# ArduinoLogger.net
KiCad netlist of a schematic drawn in EAGLE
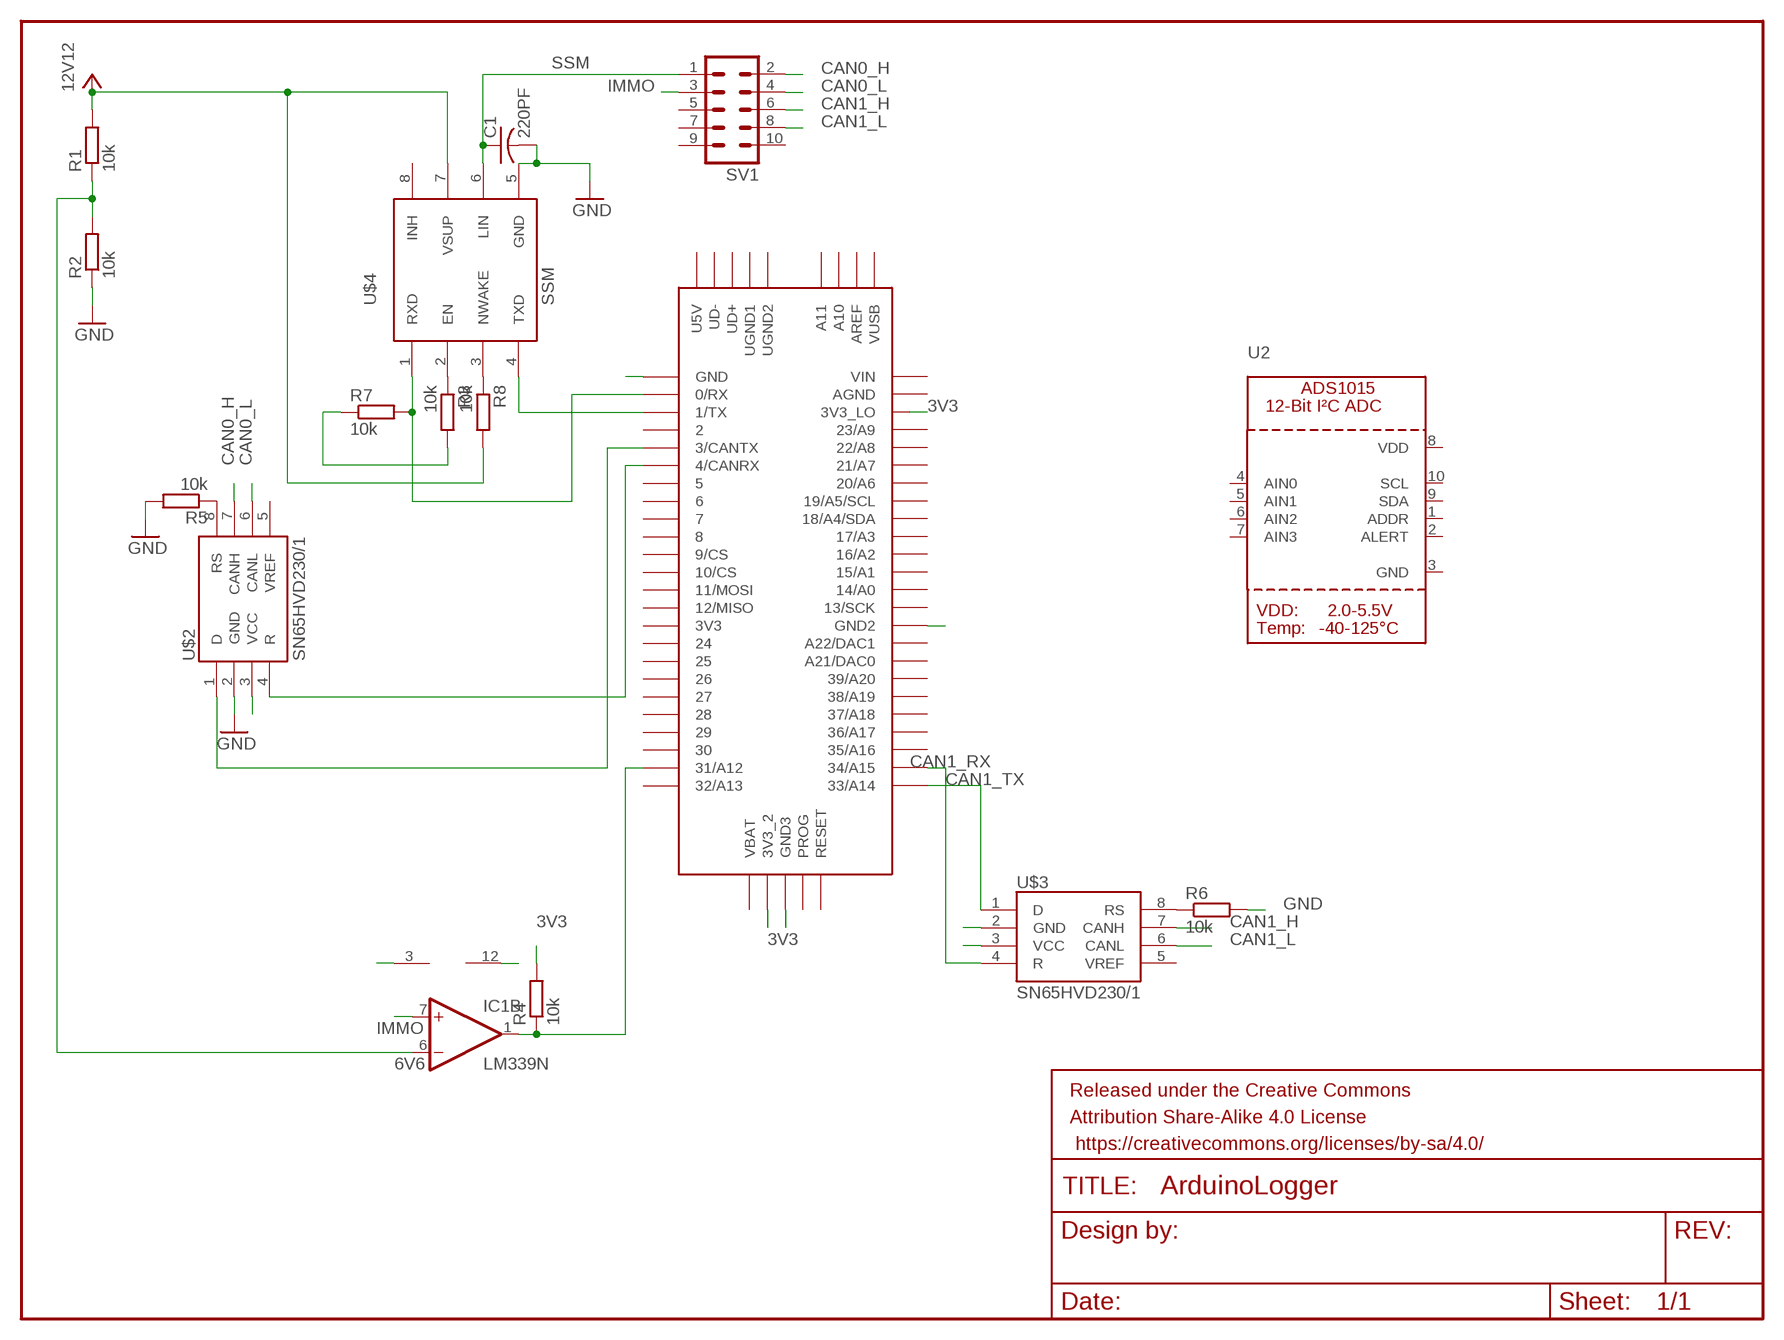
[diagram p0: schematic, sheet 1]

(export (version "E")
  (design (tool "Eeschema 10.0.6"))
  (components
    (comp (ref "C1")
      (value "220PF")
      (footprint "eagle-import:C050-024X044")
      (libsource (lib "eagle-import") (part "C-US050-024X044"))
    )
    (comp (ref "FRAME1")
      (value "FRAME-LETTER")
      (footprint "eagle-import:CREATIVE_COMMONS")
      (libsource (lib "eagle-import") (part "FRAME-LETTER"))
    )
    (comp (ref "IC1")
      (value "LM339N")
      (footprint "eagle-import:DIL14")
      (fields (field (name "SPICEPREFIX") "J"))
      (libsource (lib "eagle-import") (part "LM339N"))
    )
    (comp (ref "R1")
      (value "10k")
      (footprint "eagle-import:0204_7")
      (libsource (lib "eagle-import") (part "R0204/7"))
    )
    (comp (ref "R2")
      (value "10k")
      (footprint "eagle-import:0204_7")
      (libsource (lib "eagle-import") (part "R0204/7"))
    )
    (comp (ref "R3")
      (value "10k")
      (footprint "eagle-import:0204_7")
      (libsource (lib "eagle-import") (part "R0204/7"))
    )
    (comp (ref "R4")
      (value "10k")
      (footprint "eagle-import:0204_7")
      (libsource (lib "eagle-import") (part "R0204/7"))
    )
    (comp (ref "R5")
      (value "10k")
      (footprint "eagle-import:0204_7")
      (libsource (lib "eagle-import") (part "R0204/7"))
    )
    (comp (ref "R6")
      (value "10k")
      (footprint "eagle-import:0204_7")
      (libsource (lib "eagle-import") (part "R0204/7"))
    )
    (comp (ref "R7")
      (value "10k")
      (footprint "eagle-import:0204_7")
      (libsource (lib "eagle-import") (part "R0204/7"))
    )
    (comp (ref "R8")
      (value "10k")
      (footprint "eagle-import:0204_7")
      (libsource (lib "eagle-import") (part "R0204/7"))
    )
    (comp (ref "SV1")
      (value "MA05-2")
      (footprint "eagle-import:MA05-2")
      (libsource (lib "eagle-import") (part "MA05-2"))
    )
    (comp (ref "U$1")
      (value "TEENSY_3.5/3.6")
      (footprint "eagle-import:TEENSY_3.5_3.6")
      (libsource (lib "eagle-import") (part "TEENSY_3.5/3.6"))
    )
    (comp (ref "U$2")
      (value "SN65HVD230/1")
      (footprint "eagle-import:SO8")
      (libsource (lib "eagle-import") (part "SN65HVD230/1"))
    )
    (comp (ref "U$3")
      (value "SN65HVD230/1")
      (footprint "eagle-import:SO8")
      (libsource (lib "eagle-import") (part "SN65HVD230/1"))
    )
    (comp (ref "U$4")
      (value "SSM")
      (footprint "eagle-import:SOIC8")
      (libsource (lib "eagle-import") (part "SN65HDVA195-Q1SOIC8"))
    )
    (comp (ref "U2")
      (value "ADC_ADS1015")
      (footprint "eagle-import:MSOP10")
      (libsource (lib "eagle-import") (part "ADC_ADS1015"))
    )
  )
  (nets
    (net (code "1") (name "/3V3") (class "Default")
      (node (ref "R3") (pin "2") (pinfunction "2_2") (pintype "passive"))
      (node (ref "R4") (pin "2") (pinfunction "2_2") (pintype "passive"))
      (node (ref "R7") (pin "1") (pinfunction "1_1") (pintype "passive"))
      (node (ref "U$1") (pin "3V3_2") (pinfunction "3V3_2_3V3_2") (pintype "bidirectional"))
      (node (ref "U$1") (pin "3V3_LO") (pinfunction "3V3_LO_3V3_LO") (pintype "bidirectional"))
      (node (ref "U$2") (pin "3") (pinfunction "VCC_3") (pintype "power_in"))
      (node (ref "U$3") (pin "3") (pinfunction "VCC_3") (pintype "power_in"))
    )
    (net (code "2") (name "/6V6") (class "Default")
      (node (ref "IC1") (pin "6") (pinfunction "-IN_6") (pintype "input"))
      (node (ref "R1") (pin "1") (pinfunction "1_1") (pintype "passive"))
      (node (ref "R2") (pin "2") (pinfunction "2_2") (pintype "passive"))
    )
    (net (code "3") (name "/CAN0_H") (class "Default")
      (node (ref "SV1") (pin "2") (pinfunction "2_2") (pintype "passive"))
      (node (ref "U$2") (pin "7") (pinfunction "CANH_7") (pintype "bidirectional"))
    )
    (net (code "4") (name "/CAN0_L") (class "Default")
      (node (ref "SV1") (pin "4") (pinfunction "4_4") (pintype "passive"))
      (node (ref "U$2") (pin "6") (pinfunction "CANL_6") (pintype "bidirectional"))
    )
    (net (code "5") (name "/CAN1_H") (class "Default")
      (node (ref "SV1") (pin "6") (pinfunction "6_6") (pintype "passive"))
      (node (ref "U$3") (pin "7") (pinfunction "CANH_7") (pintype "bidirectional"))
    )
    (net (code "6") (name "/CAN1_L") (class "Default")
      (node (ref "SV1") (pin "8") (pinfunction "8_8") (pintype "passive"))
      (node (ref "U$3") (pin "6") (pinfunction "CANL_6") (pintype "bidirectional"))
    )
    (net (code "7") (name "/CAN1_RX") (class "Default")
      (node (ref "U$1") (pin "34/A15") (pinfunction "34/A15_34/A15") (pintype "bidirectional"))
      (node (ref "U$3") (pin "4") (pinfunction "R_4") (pintype "bidirectional"))
    )
    (net (code "8") (name "/CAN1_TX") (class "Default")
      (node (ref "U$1") (pin "33/A14") (pinfunction "33/A14_33/A14") (pintype "bidirectional"))
      (node (ref "U$3") (pin "1") (pinfunction "D_1") (pintype "bidirectional"))
    )
    (net (code "9") (name "/IMMO") (class "Default")
      (node (ref "IC1") (pin "7") (pinfunction "+IN_7") (pintype "input"))
      (node (ref "SV1") (pin "3") (pinfunction "3_3") (pintype "passive"))
    )
    (net (code "10") (name "/SSM") (class "Default")
      (node (ref "C1") (pin "1") (pinfunction "1_1") (pintype "passive"))
      (node (ref "SV1") (pin "1") (pinfunction "1_1") (pintype "passive"))
      (node (ref "U$4") (pin "6") (pinfunction "LIN_6") (pintype "bidirectional"))
    )
    (net (code "11") (name "12V12") (class "Default")
      (node (ref "IC1") (pin "3") (pinfunction "V+_3") (pintype "power_in"))
      (node (ref "R1") (pin "2") (pinfunction "2_2") (pintype "passive"))
      (node (ref "R8") (pin "2") (pinfunction "2_2") (pintype "passive"))
      (node (ref "U$4") (pin "7") (pinfunction "VSUP_7") (pintype "power_in"))
    )
    (net (code "12") (name "GND") (class "Default")
      (node (ref "C1") (pin "2") (pinfunction "2_2") (pintype "passive"))
      (node (ref "IC1") (pin "12") (pinfunction "GND_12") (pintype "power_in"))
      (node (ref "R2") (pin "1") (pinfunction "1_1") (pintype "passive"))
      (node (ref "R5") (pin "2") (pinfunction "2_2") (pintype "passive"))
      (node (ref "R6") (pin "2") (pinfunction "2_2") (pintype "passive"))
      (node (ref "U$1") (pin "GND") (pinfunction "GND_GND") (pintype "bidirectional"))
      (node (ref "U$1") (pin "GND2") (pinfunction "GND2_GND2") (pintype "bidirectional"))
      (node (ref "U$1") (pin "GND3") (pinfunction "GND3_GND3") (pintype "bidirectional"))
      (node (ref "U$2") (pin "2") (pinfunction "GND_2") (pintype "power_in"))
      (node (ref "U$3") (pin "2") (pinfunction "GND_2") (pintype "power_in"))
      (node (ref "U$4") (pin "5") (pinfunction "GND_5") (pintype "power_in"))
    )
    (net (code "13") (name "Net-(IC1B-OUT)") (class "Default")
      (node (ref "IC1") (pin "1") (pinfunction "OUT_1") (pintype "open_collector"))
      (node (ref "R4") (pin "1") (pinfunction "1_1") (pintype "passive"))
      (node (ref "U$1") (pin "31/A12") (pinfunction "31/A12_31/A12") (pintype "bidirectional"))
    )
    (net (code "14") (name "Net-(U$2-D)") (class "Default")
      (node (ref "U$1") (pin "3/CANTX") (pinfunction "3/CANTX_3/CANTX") (pintype "bidirectional"))
      (node (ref "U$2") (pin "1") (pinfunction "D_1") (pintype "bidirectional"))
    )
    (net (code "15") (name "Net-(U$2-R)") (class "Default")
      (node (ref "U$1") (pin "4/CANRX") (pinfunction "4/CANRX_4/CANRX") (pintype "bidirectional"))
      (node (ref "U$2") (pin "4") (pinfunction "R_4") (pintype "bidirectional"))
    )
    (net (code "16") (name "Net-(U$2-RS)") (class "Default")
      (node (ref "R5") (pin "1") (pinfunction "1_1") (pintype "passive"))
      (node (ref "U$2") (pin "8") (pinfunction "RS_8") (pintype "bidirectional"))
    )
    (net (code "17") (name "Net-(U$3-RS)") (class "Default")
      (node (ref "R6") (pin "1") (pinfunction "1_1") (pintype "passive"))
      (node (ref "U$3") (pin "8") (pinfunction "RS_8") (pintype "bidirectional"))
    )
    (net (code "18") (name "Net-(U$4-EN)") (class "Default")
      (node (ref "R3") (pin "1") (pinfunction "1_1") (pintype "passive"))
      (node (ref "U$4") (pin "2") (pinfunction "EN_2") (pintype "input"))
    )
    (net (code "19") (name "Net-(U$4-NWAKE)") (class "Default")
      (node (ref "R8") (pin "1") (pinfunction "1_1") (pintype "passive"))
      (node (ref "U$4") (pin "3") (pinfunction "NWAKE_3") (pintype "input"))
    )
    (net (code "20") (name "Net-(U$4-RXD)") (class "Default")
      (node (ref "R7") (pin "2") (pinfunction "2_2") (pintype "passive"))
      (node (ref "U$1") (pin "0/RX") (pinfunction "0/RX_0/RX") (pintype "bidirectional"))
      (node (ref "U$4") (pin "1") (pinfunction "RXD_1") (pintype "output"))
    )
    (net (code "21") (name "Net-(U$4-TXD)") (class "Default")
      (node (ref "U$1") (pin "1/TX") (pinfunction "1/TX_1/TX") (pintype "bidirectional"))
      (node (ref "U$4") (pin "4") (pinfunction "TXD_4") (pintype "input"))
    )
    (net (code "22") (name "unconnected-(SV1-Pad5)") (class "Default")
      (node (ref "SV1") (pin "5") (pinfunction "5_5") (pintype "passive"))
    )
    (net (code "23") (name "unconnected-(SV1-Pad7)") (class "Default")
      (node (ref "SV1") (pin "7") (pinfunction "7_7") (pintype "passive"))
    )
    (net (code "24") (name "unconnected-(SV1-Pad9)") (class "Default")
      (node (ref "SV1") (pin "9") (pinfunction "9_9") (pintype "passive"))
    )
    (net (code "25") (name "unconnected-(SV1-Pad10)") (class "Default")
      (node (ref "SV1") (pin "10") (pinfunction "10_10") (pintype "passive"))
    )
    (net (code "26") (name "unconnected-(U$1-A21{slash}DAC0-Pad21{slash}DAC0)") (class "Default")
      (node (ref "U$1") (pin "21/DAC0") (pinfunction "A21/DAC0_21/DAC0") (pintype "bidirectional"))
    )
    (net (code "27") (name "unconnected-(U$1-Pad2)") (class "Default")
      (node (ref "U$1") (pin "2") (pinfunction "2_2") (pintype "bidirectional"))
    )
    (net (code "28") (name "unconnected-(U$1-Pad3V3)") (class "Default")
      (node (ref "U$1") (pin "3V3") (pinfunction "3V3_3V3") (pintype "bidirectional"))
    )
    (net (code "29") (name "unconnected-(U$1-Pad5)") (class "Default")
      (node (ref "U$1") (pin "5") (pinfunction "5_5") (pintype "bidirectional"))
    )
    (net (code "30") (name "unconnected-(U$1-Pad6)") (class "Default")
      (node (ref "U$1") (pin "6") (pinfunction "6_6") (pintype "bidirectional"))
    )
    (net (code "31") (name "unconnected-(U$1-Pad7)") (class "Default")
      (node (ref "U$1") (pin "7") (pinfunction "7_7") (pintype "bidirectional"))
    )
    (net (code "32") (name "unconnected-(U$1-Pad8)") (class "Default")
      (node (ref "U$1") (pin "8") (pinfunction "8_8") (pintype "bidirectional"))
    )
    (net (code "33") (name "unconnected-(U$1-Pad9{slash}CS)") (class "Default")
      (node (ref "U$1") (pin "9/CS") (pinfunction "9/CS_9/CS") (pintype "bidirectional"))
    )
    (net (code "34") (name "unconnected-(U$1-Pad10{slash}CS)") (class "Default")
      (node (ref "U$1") (pin "10/CS") (pinfunction "10/CS_10/CS") (pintype "bidirectional"))
    )
    (net (code "35") (name "unconnected-(U$1-Pad11{slash}MOSI)") (class "Default")
      (node (ref "U$1") (pin "11/MOSI") (pinfunction "11/MOSI_11/MOSI") (pintype "bidirectional"))
    )
    (net (code "36") (name "unconnected-(U$1-Pad12{slash}MISO)") (class "Default")
      (node (ref "U$1") (pin "12/MISO") (pinfunction "12/MISO_12/MISO") (pintype "bidirectional"))
    )
    (net (code "37") (name "unconnected-(U$1-Pad13{slash}SCK)") (class "Default")
      (node (ref "U$1") (pin "13/SCK") (pinfunction "13/SCK_13/SCK") (pintype "bidirectional"))
    )
    (net (code "38") (name "unconnected-(U$1-Pad14{slash}A0)") (class "Default")
      (node (ref "U$1") (pin "14/A0") (pinfunction "14/A0_14/A0") (pintype "bidirectional"))
    )
    (net (code "39") (name "unconnected-(U$1-Pad15{slash}A1)") (class "Default")
      (node (ref "U$1") (pin "15/A1") (pinfunction "15/A1_15/A1") (pintype "bidirectional"))
    )
    (net (code "40") (name "unconnected-(U$1-Pad16{slash}A2)") (class "Default")
      (node (ref "U$1") (pin "16/A2") (pinfunction "16/A2_16/A2") (pintype "bidirectional"))
    )
    (net (code "41") (name "unconnected-(U$1-Pad17{slash}A3)") (class "Default")
      (node (ref "U$1") (pin "17/A3") (pinfunction "17/A3_17/A3") (pintype "bidirectional"))
    )
    (net (code "42") (name "unconnected-(U$1-Pad18{slash}A4{slash}SDA)") (class "Default")
      (node (ref "U$1") (pin "18/A4/SDA") (pinfunction "18/A4/SDA_18/A4/SDA") (pintype "bidirectional"))
    )
    (net (code "43") (name "unconnected-(U$1-Pad19{slash}A5{slash}SCL)") (class "Default")
      (node (ref "U$1") (pin "19/A5/SCL") (pinfunction "19/A5/SCL_19/A5/SCL") (pintype "bidirectional"))
    )
    (net (code "44") (name "unconnected-(U$1-Pad20{slash}A6)") (class "Default")
      (node (ref "U$1") (pin "20/A6") (pinfunction "20/A6_20/A6") (pintype "bidirectional"))
    )
    (net (code "45") (name "unconnected-(U$1-Pad21{slash}A7)") (class "Default")
      (node (ref "U$1") (pin "21/A7") (pinfunction "21/A7_21/A7") (pintype "bidirectional"))
    )
    (net (code "46") (name "unconnected-(U$1-Pad22{slash}A8)") (class "Default")
      (node (ref "U$1") (pin "22/A8") (pinfunction "22/A8_22/A8") (pintype "bidirectional"))
    )
    (net (code "47") (name "unconnected-(U$1-Pad23{slash}A9)") (class "Default")
      (node (ref "U$1") (pin "23/A9") (pinfunction "23/A9_23/A9") (pintype "bidirectional"))
    )
    (net (code "48") (name "unconnected-(U$1-Pad24)") (class "Default")
      (node (ref "U$1") (pin "24") (pinfunction "24_24") (pintype "bidirectional"))
    )
    (net (code "49") (name "unconnected-(U$1-Pad25)") (class "Default")
      (node (ref "U$1") (pin "25") (pinfunction "25_25") (pintype "bidirectional"))
    )
    (net (code "50") (name "unconnected-(U$1-Pad26)") (class "Default")
      (node (ref "U$1") (pin "26") (pinfunction "26_26") (pintype "bidirectional"))
    )
    (net (code "51") (name "unconnected-(U$1-Pad27)") (class "Default")
      (node (ref "U$1") (pin "27") (pinfunction "27_27") (pintype "bidirectional"))
    )
    (net (code "52") (name "unconnected-(U$1-Pad28)") (class "Default")
      (node (ref "U$1") (pin "28") (pinfunction "28_28") (pintype "bidirectional"))
    )
    (net (code "53") (name "unconnected-(U$1-Pad29)") (class "Default")
      (node (ref "U$1") (pin "29") (pinfunction "29_29") (pintype "bidirectional"))
    )
    (net (code "54") (name "unconnected-(U$1-Pad30)") (class "Default")
      (node (ref "U$1") (pin "30") (pinfunction "30_30") (pintype "bidirectional"))
    )
    (net (code "55") (name "unconnected-(U$1-Pad32{slash}A13)") (class "Default")
      (node (ref "U$1") (pin "32/A13") (pinfunction "32/A13_32/A13") (pintype "bidirectional"))
    )
    (net (code "56") (name "unconnected-(U$1-Pad35{slash}A16)") (class "Default")
      (node (ref "U$1") (pin "35/A16") (pinfunction "35/A16_35/A16") (pintype "bidirectional"))
    )
    (net (code "57") (name "unconnected-(U$1-Pad36{slash}A17)") (class "Default")
      (node (ref "U$1") (pin "36/A17") (pinfunction "36/A17_36/A17") (pintype "bidirectional"))
    )
    (net (code "58") (name "unconnected-(U$1-Pad37{slash}A18)") (class "Default")
      (node (ref "U$1") (pin "37/A18") (pinfunction "37/A18_37/A18") (pintype "bidirectional"))
    )
    (net (code "59") (name "unconnected-(U$1-Pad38{slash}A19)") (class "Default")
      (node (ref "U$1") (pin "38/A19") (pinfunction "38/A19_38/A19") (pintype "bidirectional"))
    )
    (net (code "60") (name "unconnected-(U$1-Pad39{slash}A20)") (class "Default")
      (node (ref "U$1") (pin "39/A20") (pinfunction "39/A20_39/A20") (pintype "bidirectional"))
    )
    (net (code "61") (name "unconnected-(U$1-PadA10)") (class "Default")
      (node (ref "U$1") (pin "A10") (pinfunction "A10_A10") (pintype "bidirectional"))
    )
    (net (code "62") (name "unconnected-(U$1-PadA11)") (class "Default")
      (node (ref "U$1") (pin "A11") (pinfunction "A11_A11") (pintype "bidirectional"))
    )
    (net (code "63") (name "unconnected-(U$1-PadA22{slash}DAC1)") (class "Default")
      (node (ref "U$1") (pin "A22/DAC1") (pinfunction "A22/DAC1_A22/DAC1") (pintype "bidirectional"))
    )
    (net (code "64") (name "unconnected-(U$1-PadAGND)") (class "Default")
      (node (ref "U$1") (pin "AGND") (pinfunction "AGND_AGND") (pintype "bidirectional"))
    )
    (net (code "65") (name "unconnected-(U$1-PadAREF)") (class "Default")
      (node (ref "U$1") (pin "AREF") (pinfunction "AREF_AREF") (pintype "bidirectional"))
    )
    (net (code "66") (name "unconnected-(U$1-PadPROG)") (class "Default")
      (node (ref "U$1") (pin "PROG") (pinfunction "PROG_PROG") (pintype "bidirectional"))
    )
    (net (code "67") (name "unconnected-(U$1-PadRESET)") (class "Default")
      (node (ref "U$1") (pin "RESET") (pinfunction "RESET_RESET") (pintype "bidirectional"))
    )
    (net (code "68") (name "unconnected-(U$1-PadU5V)") (class "Default")
      (node (ref "U$1") (pin "U5V") (pinfunction "U5V_U5V") (pintype "bidirectional"))
    )
    (net (code "69") (name "unconnected-(U$1-PadUD+)") (class "Default")
      (node (ref "U$1") (pin "UD+") (pinfunction "UD+_UD+") (pintype "bidirectional"))
    )
    (net (code "70") (name "unconnected-(U$1-PadUD-)") (class "Default")
      (node (ref "U$1") (pin "UD-") (pinfunction "UD-_UD-") (pintype "bidirectional"))
    )
    (net (code "71") (name "unconnected-(U$1-PadUGND1)") (class "Default")
      (node (ref "U$1") (pin "UGND1") (pinfunction "UGND1_UGND1") (pintype "bidirectional"))
    )
    (net (code "72") (name "unconnected-(U$1-PadUGND2)") (class "Default")
      (node (ref "U$1") (pin "UGND2") (pinfunction "UGND2_UGND2") (pintype "bidirectional"))
    )
    (net (code "73") (name "unconnected-(U$1-PadVBAT)") (class "Default")
      (node (ref "U$1") (pin "VBAT") (pinfunction "VBAT_VBAT") (pintype "bidirectional"))
    )
    (net (code "74") (name "unconnected-(U$1-PadVIN)") (class "Default")
      (node (ref "U$1") (pin "VIN") (pinfunction "VIN_VIN") (pintype "bidirectional"))
    )
    (net (code "75") (name "unconnected-(U$1-PadVUSB)") (class "Default")
      (node (ref "U$1") (pin "VUSB") (pinfunction "VUSB_VUSB") (pintype "bidirectional"))
    )
    (net (code "76") (name "unconnected-(U$2-VREF-Pad5)") (class "Default")
      (node (ref "U$2") (pin "5") (pinfunction "VREF_5") (pintype "bidirectional"))
    )
    (net (code "77") (name "unconnected-(U$3-VREF-Pad5)") (class "Default")
      (node (ref "U$3") (pin "5") (pinfunction "VREF_5") (pintype "bidirectional"))
    )
    (net (code "78") (name "unconnected-(U$4-INH-Pad8)") (class "Default")
      (node (ref "U$4") (pin "8") (pinfunction "INH_8") (pintype "output"))
    )
    (net (code "79") (name "unconnected-(U2-ADDR-Pad1)") (class "Default")
      (node (ref "U2") (pin "1") (pinfunction "ADDR_1") (pintype "bidirectional"))
    )
    (net (code "80") (name "unconnected-(U2-AIN0-Pad4)") (class "Default")
      (node (ref "U2") (pin "4") (pinfunction "AIN0_4") (pintype "bidirectional"))
    )
    (net (code "81") (name "unconnected-(U2-AIN1-Pad5)") (class "Default")
      (node (ref "U2") (pin "5") (pinfunction "AIN1_5") (pintype "bidirectional"))
    )
    (net (code "82") (name "unconnected-(U2-AIN2-Pad6)") (class "Default")
      (node (ref "U2") (pin "6") (pinfunction "AIN2_6") (pintype "bidirectional"))
    )
    (net (code "83") (name "unconnected-(U2-AIN3-Pad7)") (class "Default")
      (node (ref "U2") (pin "7") (pinfunction "AIN3_7") (pintype "bidirectional"))
    )
    (net (code "84") (name "unconnected-(U2-ALERT-Pad2)") (class "Default")
      (node (ref "U2") (pin "2") (pinfunction "ALERT_2") (pintype "bidirectional"))
    )
    (net (code "85") (name "unconnected-(U2-GND-Pad3)") (class "Default")
      (node (ref "U2") (pin "3") (pinfunction "GND_3") (pintype "bidirectional"))
    )
    (net (code "86") (name "unconnected-(U2-SCL-Pad10)") (class "Default")
      (node (ref "U2") (pin "10") (pinfunction "SCL_10") (pintype "bidirectional"))
    )
    (net (code "87") (name "unconnected-(U2-SDA-Pad9)") (class "Default")
      (node (ref "U2") (pin "9") (pinfunction "SDA_9") (pintype "bidirectional"))
    )
    (net (code "88") (name "unconnected-(U2-VDD-Pad8)") (class "Default")
      (node (ref "U2") (pin "8") (pinfunction "VDD_8") (pintype "bidirectional"))
    )
  )
)
